# Switch.net
KiCad netlist of a schematic drawn in Altium Designer
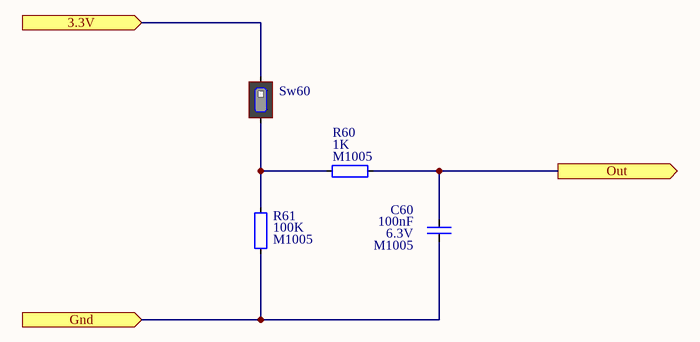
[diagram p0: Switch.SchDoc]

(export (version "E")
  (design (tool "Eeschema 10.0.6"))
  (components
    (comp (ref "C60")
      (value "100nF")
      (footprint "Capacitor_Ceramic_M1005_I0402")
      (description "Cap, Cer, 100nF, 6.3V, M1005")
      (fields
        (field (name "VOLTAGE") "6.3V")
        (field (name "MANUFACTURER PART NUMBER") "04026D104KAT4A")
        (field (name "MANUFACTURER") "Kyocera")
        (field (name "PACKAGE") "M1005")
      )
      (libsource (lib "Capacitor") (part "Capacitor_Ceramic"))
    )
    (comp (ref "R60")
      (value "1K")
      (footprint "Resistor_Smd_M1005_I0402")
      (description "Res, 1K, 1%, M1005")
      (fields
        (field (name "TOLERANCE") "1%")
        (field (name "MANUFACTURER") "Yageo")
        (field (name "PACKAGE") "M1005")
      )
      (libsource (lib "Resistor") (part "Resistor"))
    )
    (comp (ref "R61")
      (value "100K")
      (footprint "Resistor_Smd_M1005_I0402")
      (description "Res, 100K, 1%, M1005")
      (fields
        (field (name "TOLERANCE") "1%")
        (field (name "MANUFACTURER") "Yageo")
        (field (name "PACKAGE") "M1005")
      )
      (libsource (lib "Resistor") (part "Resistor"))
    )
    (comp (ref "Sw60")
      (value "Slide, SPST")
      (footprint "Slide, SPST - C&K, SDA01HxS")
      (description "Switch, Slide, SPST, SMD")
      (fields (field (name "MANUFACTURER") "C&K") (field (name "MANUFACTURER PART NUMBER") "SDA01H1SBD"))
      (libsource (lib "Switch") (part "Slide, SPST"))
    )
  )
  (nets
    (net (code "1") (name "/3.3V") (class "Default")
      (node (ref "Sw60") (pin "A") (pinfunction "A_A") (pintype "passive"))
    )
    (net (code "2") (name "/Gnd") (class "Default")
      (node (ref "C60") (pin "2") (pinfunction "2_2") (pintype "passive"))
      (node (ref "R61") (pin "2") (pinfunction "2_2") (pintype "passive"))
    )
    (net (code "3") (name "/Out") (class "Default")
      (node (ref "C60") (pin "1") (pinfunction "1_1") (pintype "passive"))
      (node (ref "R60") (pin "2") (pinfunction "2_2") (pintype "passive"))
    )
    (net (code "4") (name "Net-(R60-Pad1)") (class "Default")
      (node (ref "R60") (pin "1") (pinfunction "1_1") (pintype "passive"))
      (node (ref "R61") (pin "1") (pinfunction "1_1") (pintype "passive"))
      (node (ref "Sw60") (pin "B") (pinfunction "B_B") (pintype "passive"))
    )
  )
)
